# proyecto.net
KiCad netlist of a schematic drawn in EAGLE
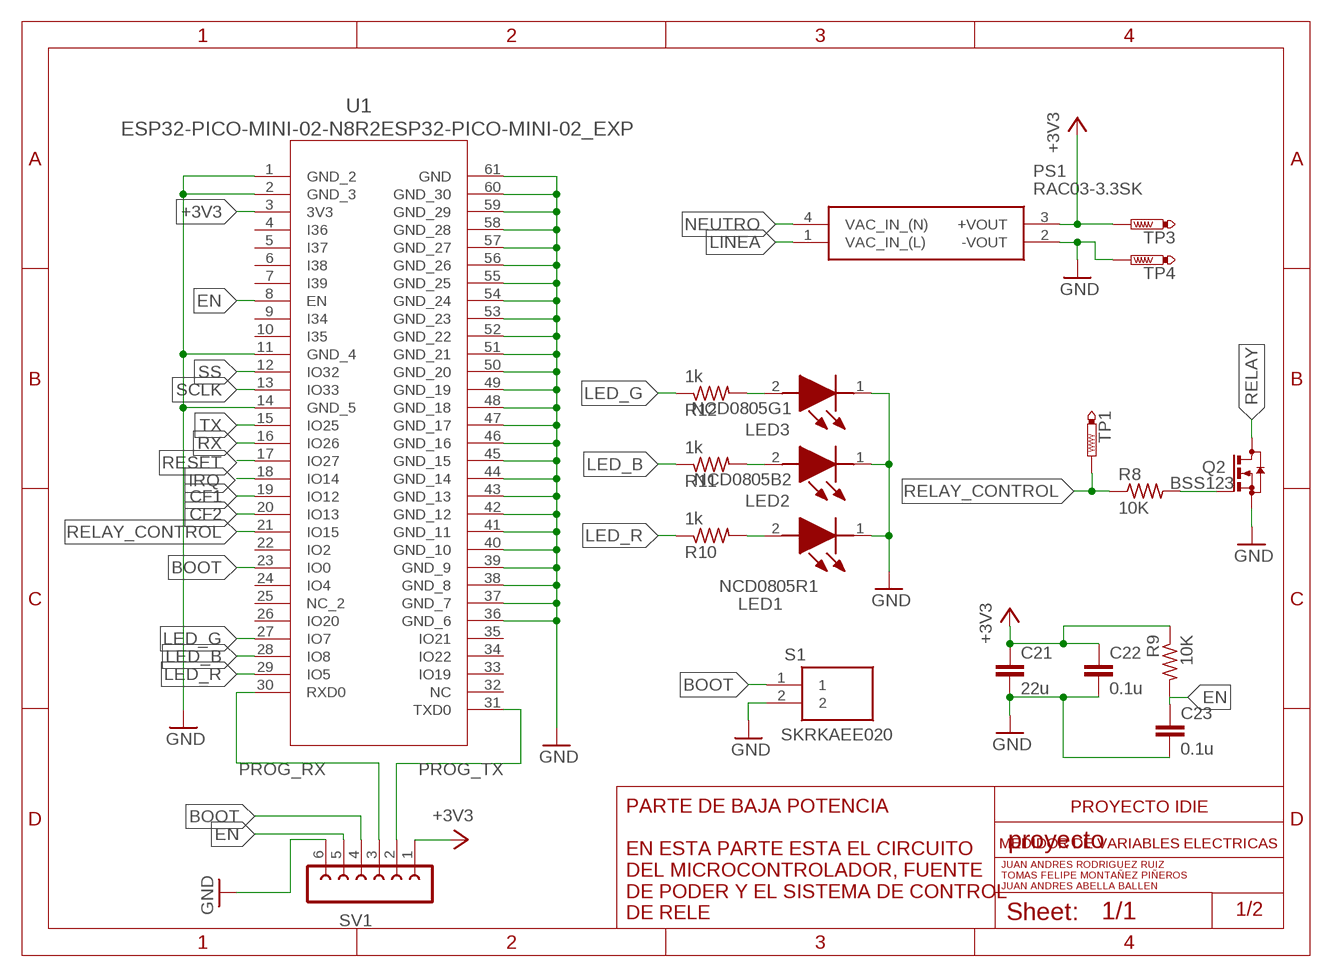
[diagram p0: schematic, sheet 1, part 1 of 2]
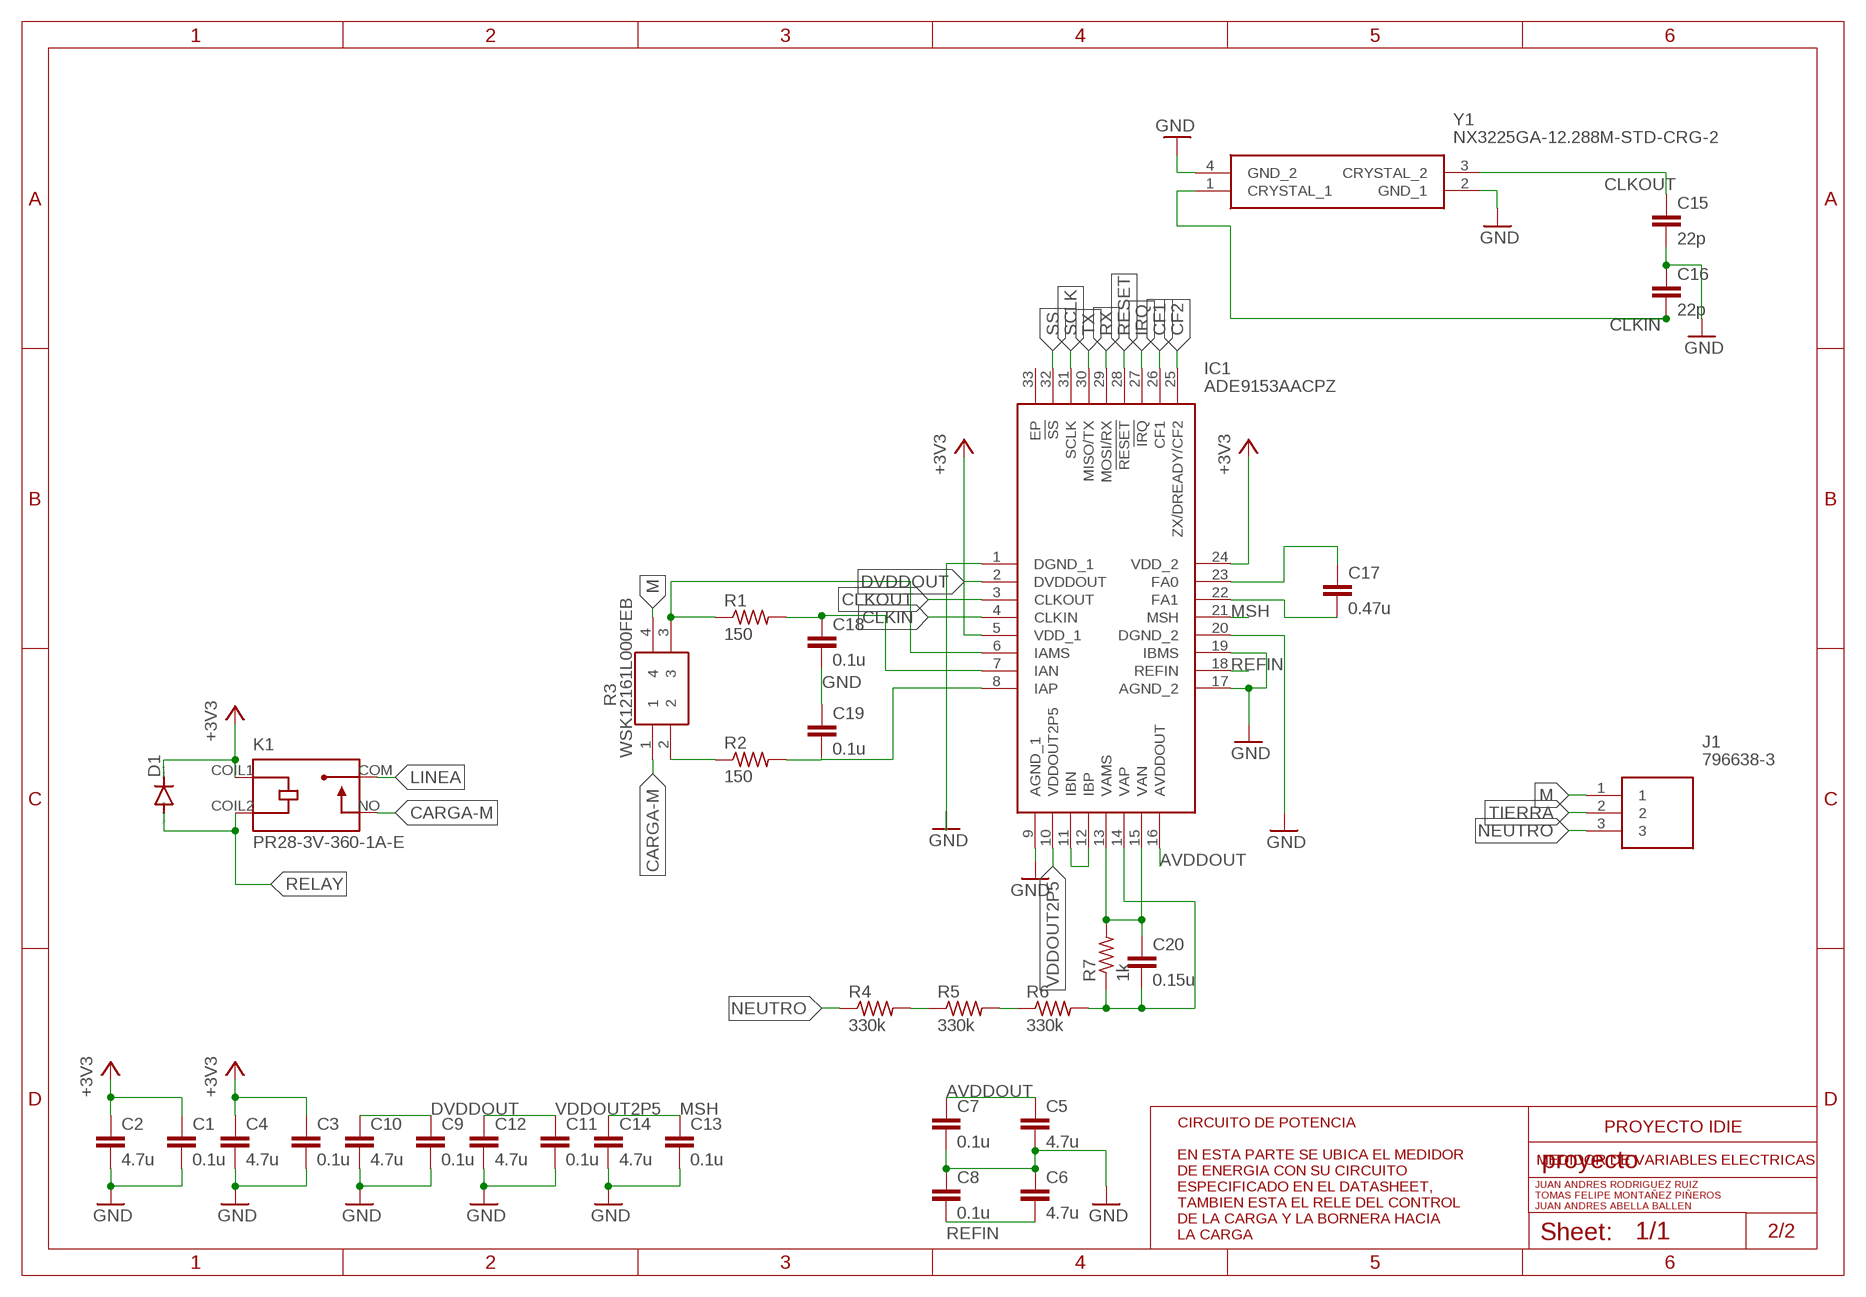
[diagram p1: schematic, sheet 1, part 2 of 2]

(export (version "E")
  (design (tool "Eeschema 10.0.6"))
  (components
    (comp (ref "C1")
      (value "0.1u")
      (footprint "eagle-import:C0402K")
      (libsource (lib "eagle-import") (part "C-EUC0402K"))
    )
    (comp (ref "C2")
      (value "4.7u")
      (footprint "eagle-import:C0402K")
      (libsource (lib "eagle-import") (part "C-EUC0402K"))
    )
    (comp (ref "C3")
      (value "0.1u")
      (footprint "eagle-import:C0402K")
      (libsource (lib "eagle-import") (part "C-EUC0402K"))
    )
    (comp (ref "C4")
      (value "4.7u")
      (footprint "eagle-import:C0402K")
      (libsource (lib "eagle-import") (part "C-EUC0402K"))
    )
    (comp (ref "C5")
      (value "4.7u")
      (footprint "eagle-import:C0402K")
      (libsource (lib "eagle-import") (part "C-EUC0402K"))
    )
    (comp (ref "C6")
      (value "4.7u")
      (footprint "eagle-import:C0402K")
      (libsource (lib "eagle-import") (part "C-EUC0402K"))
    )
    (comp (ref "C7")
      (value "0.1u")
      (footprint "eagle-import:C0402K")
      (libsource (lib "eagle-import") (part "C-EUC0402K"))
    )
    (comp (ref "C8")
      (value "0.1u")
      (footprint "eagle-import:C0402K")
      (libsource (lib "eagle-import") (part "C-EUC0402K"))
    )
    (comp (ref "C9")
      (value "0.1u")
      (footprint "eagle-import:C0402K")
      (libsource (lib "eagle-import") (part "C-EUC0402K"))
    )
    (comp (ref "C10")
      (value "4.7u")
      (footprint "eagle-import:C0402K")
      (libsource (lib "eagle-import") (part "C-EUC0402K"))
    )
    (comp (ref "C11")
      (value "0.1u")
      (footprint "eagle-import:C0402K")
      (libsource (lib "eagle-import") (part "C-EUC0402K"))
    )
    (comp (ref "C12")
      (value "4.7u")
      (footprint "eagle-import:C0402K")
      (libsource (lib "eagle-import") (part "C-EUC0402K"))
    )
    (comp (ref "C13")
      (value "0.1u")
      (footprint "eagle-import:C0402K")
      (libsource (lib "eagle-import") (part "C-EUC0402K"))
    )
    (comp (ref "C14")
      (value "4.7u")
      (footprint "eagle-import:C0402K")
      (libsource (lib "eagle-import") (part "C-EUC0402K"))
    )
    (comp (ref "C15")
      (value "22p")
      (footprint "eagle-import:C0402K")
      (libsource (lib "eagle-import") (part "C-EUC0402K"))
    )
    (comp (ref "C16")
      (value "22p")
      (footprint "eagle-import:C0402K")
      (libsource (lib "eagle-import") (part "C-EUC0402K"))
    )
    (comp (ref "C17")
      (value "0.47u")
      (footprint "eagle-import:C0402K")
      (libsource (lib "eagle-import") (part "C-EUC0402K"))
    )
    (comp (ref "C18")
      (value "0.1u")
      (footprint "eagle-import:C0402K")
      (libsource (lib "eagle-import") (part "C-EUC0402K"))
    )
    (comp (ref "C19")
      (value "0.1u")
      (footprint "eagle-import:C0402K")
      (libsource (lib "eagle-import") (part "C-EUC0402K"))
    )
    (comp (ref "C20")
      (value "0.15u")
      (footprint "eagle-import:C0402K")
      (libsource (lib "eagle-import") (part "C-EUC0402K"))
    )
    (comp (ref "C21")
      (value "22u")
      (footprint "eagle-import:C0402K")
      (libsource (lib "eagle-import") (part "C-EUC0402K"))
    )
    (comp (ref "C22")
      (value "0.1u")
      (footprint "eagle-import:C0402K")
      (libsource (lib "eagle-import") (part "C-EUC0402K"))
    )
    (comp (ref "C23")
      (value "0.1u")
      (footprint "eagle-import:C0402K")
      (libsource (lib "eagle-import") (part "C-EUC0402K"))
    )
    (comp (ref "D1")
      (value "DIODE-SMB")
      (footprint "eagle-import:SMB")
      (libsource (lib "eagle-import") (part "DIODE-SMB"))
    )
    (comp (ref "IC1")
      (value "ADE9153AACPZ")
      (footprint "eagle-import:QFN50P500X500X80-33N")
      (fields (field (name "MOUSER_PART_NUMBER") "584-ADE9153AACPZ"))
      (libsource (lib "eagle-import") (part "ADE9153AACPZ"))
    )
    (comp (ref "J1")
      (value "796638-3")
      (footprint "eagle-import:SHDRRA3W102P0X508_1X3_1706X120")
      (fields (field (name "MOUSER_PART_NUMBER") "571-7966383"))
      (libsource (lib "eagle-import") (part "796638-3"))
    )
    (comp (ref "K1")
      (value "PR28-3V-360-1A-E")
      (footprint "eagle-import:RELAY_PR28-3V-360-1A-E")
      (fields (field (name "MF") "CUI Devices"))
      (libsource (lib "eagle-import") (part "PR28-3V-360-1A-E"))
    )
    (comp (ref "LED1")
      (value "NCD0805R1")
      (footprint "eagle-import:LEDC2012X120N")
      (libsource (lib "eagle-import") (part "NCD0805R1"))
    )
    (comp (ref "LED2")
      (value "NCD0805B2")
      (footprint "eagle-import:LEDC2012X120N")
      (libsource (lib "eagle-import") (part "NCD0805B2"))
    )
    (comp (ref "LED3")
      (value "NCD0805G1")
      (footprint "eagle-import:LEDC2012X120N")
      (libsource (lib "eagle-import") (part "NCD0805G1"))
    )
    (comp (ref "PS1")
      (value "RAC03-3.3SK")
      (footprint "eagle-import:RAC0305SK")
      (fields (field (name "MOUSER_PART_NUMBER") "919-RAC03-3.3SK"))
      (libsource (lib "eagle-import") (part "RAC03-3.3SK"))
    )
    (comp (ref "Q2")
      (value "BSS123")
      (footprint "eagle-import:SOT23")
      (libsource (lib "eagle-import") (part "BSS123"))
    )
    (comp (ref "R1")
      (value "150")
      (footprint "eagle-import:R0402")
      (libsource (lib "eagle-import") (part "R-US_R0402"))
    )
    (comp (ref "R2")
      (value "150")
      (footprint "eagle-import:R0402")
      (libsource (lib "eagle-import") (part "R-US_R0402"))
    )
    (comp (ref "R3")
      (value "WSK12161L000FEB")
      (footprint "eagle-import:WSK12161L000FEB")
      (fields (field (name "MOUSER_PART_NUMBER") "71-WSK12161L000FEB"))
      (libsource (lib "eagle-import") (part "WSK12161L000FEB"))
    )
    (comp (ref "R4")
      (value "330k")
      (footprint "eagle-import:R0603")
      (libsource (lib "eagle-import") (part "R-US_R0603"))
    )
    (comp (ref "R5")
      (value "330k")
      (footprint "eagle-import:R0603")
      (libsource (lib "eagle-import") (part "R-US_R0603"))
    )
    (comp (ref "R6")
      (value "330k")
      (footprint "eagle-import:R0603")
      (libsource (lib "eagle-import") (part "R-US_R0603"))
    )
    (comp (ref "R7")
      (value "1k")
      (footprint "eagle-import:R0603")
      (libsource (lib "eagle-import") (part "R-US_R0603"))
    )
    (comp (ref "R8")
      (value "10K")
      (footprint "eagle-import:R0402")
      (libsource (lib "eagle-import") (part "R-US_R0402"))
    )
    (comp (ref "R9")
      (value "10K")
      (footprint "eagle-import:R0402")
      (libsource (lib "eagle-import") (part "R-US_R0402"))
    )
    (comp (ref "R10")
      (value "1k")
      (footprint "eagle-import:R0402")
      (libsource (lib "eagle-import") (part "R-US_R0402"))
    )
    (comp (ref "R11")
      (value "1k")
      (footprint "eagle-import:R0402")
      (libsource (lib "eagle-import") (part "R-US_R0402"))
    )
    (comp (ref "R12")
      (value "1k")
      (footprint "eagle-import:R0402")
      (libsource (lib "eagle-import") (part "R-US_R0402"))
    )
    (comp (ref "S1")
      (value "SKRKAEE020")
      (footprint "eagle-import:SKRKAEE020")
      (fields (field (name "MOUSER_PART_NUMBER") "688-SKRKAEE020"))
      (libsource (lib "eagle-import") (part "SKRKAEE020"))
    )
    (comp (ref "SV1")
      (value "FE06-1")
      (footprint "eagle-import:FE06")
      (libsource (lib "eagle-import") (part "FE06-1"))
    )
    (comp (ref "TP1")
      (value "PTR1TP10R")
      (footprint "eagle-import:TP10R")
      (libsource (lib "eagle-import") (part "PTR1TP10R"))
    )
    (comp (ref "TP3")
      (value "PTR1TP10R")
      (footprint "eagle-import:TP10R")
      (libsource (lib "eagle-import") (part "PTR1TP10R"))
    )
    (comp (ref "TP4")
      (value "PTR1TP10R")
      (footprint "eagle-import:TP10R")
      (libsource (lib "eagle-import") (part "PTR1TP10R"))
    )
    (comp (ref "U1")
      (value "ESP32-PICO-MINI-02-N8R2ESP32-PICO-MINI-02_EXP")
      (footprint "eagle-import:ESP32-PICO-MINI-02_EXP")
      (fields
        (field (name "MANUFACTURER_PART_NUMBER") "ESP32-PICO-MINI-02-N8R2")
        (field (name "COPYRIGHT") "Copyright (C) 2024 Ultra Librarian. All rights reserved.")
      )
      (libsource (lib "eagle-import") (part "ESP32-PICO-MINI-02-N8R2ESP32-PICO-MINI-02_EXP"))
    )
    (comp (ref "Y1")
      (value "NX3225GA-12.288M-STD-CRG-2")
      (footprint "eagle-import:NX3225GA12288MSTDCRG2")
      (libsource (lib "eagle-import") (part "NX3225GA-12.288M-STD-CRG-2"))
    )
  )
  (nets
    (net (code "1") (name "+3V3") (class "Default")
      (node (ref "C1") (pin "1") (pinfunction "1_1") (pintype "passive"))
      (node (ref "C2") (pin "1") (pinfunction "1_1") (pintype "passive"))
      (node (ref "C21") (pin "1") (pinfunction "1_1") (pintype "passive"))
      (node (ref "C22") (pin "1") (pinfunction "1_1") (pintype "passive"))
      (node (ref "C3") (pin "1") (pinfunction "1_1") (pintype "passive"))
      (node (ref "C4") (pin "1") (pinfunction "1_1") (pintype "passive"))
      (node (ref "D1") (pin "C") (pinfunction "C_C") (pintype "passive"))
      (node (ref "IC1") (pin "24") (pinfunction "VDD_2_24") (pintype "bidirectional"))
      (node (ref "IC1") (pin "5") (pinfunction "VDD_1_5") (pintype "bidirectional"))
      (node (ref "K1") (pin "COIL1") (pinfunction "COIL1_COIL1") (pintype "passive"))
      (node (ref "PS1") (pin "3") (pinfunction "+VOUT_3") (pintype "bidirectional"))
      (node (ref "R9") (pin "1") (pinfunction "1_1") (pintype "passive"))
      (node (ref "SV1") (pin "1") (pinfunction "1_1") (pintype "passive"))
      (node (ref "TP3") (pin "TP") (pinfunction "TP_TP") (pintype "input"))
      (node (ref "U1") (pin "3") (pinfunction "3V3_3") (pintype "power_in"))
    )
    (net (code "2") (name "/AVDDOUT") (class "Default")
      (node (ref "C5") (pin "1") (pinfunction "1_1") (pintype "passive"))
      (node (ref "C7") (pin "1") (pinfunction "1_1") (pintype "passive"))
      (node (ref "IC1") (pin "16") (pinfunction "AVDDOUT_16") (pintype "bidirectional"))
    )
    (net (code "3") (name "/MSH") (class "Default")
      (node (ref "C13") (pin "1") (pinfunction "1_1") (pintype "passive"))
      (node (ref "C14") (pin "1") (pinfunction "1_1") (pintype "passive"))
      (node (ref "IC1") (pin "21") (pinfunction "MSH_21") (pintype "bidirectional"))
    )
    (net (code "4") (name "/PROG_RX") (class "Default")
      (node (ref "SV1") (pin "3") (pinfunction "3_3") (pintype "passive"))
      (node (ref "U1") (pin "30") (pinfunction "RXD0_30") (pintype "bidirectional"))
    )
    (net (code "5") (name "/PROG_TX") (class "Default")
      (node (ref "SV1") (pin "2") (pinfunction "2_2") (pintype "passive"))
      (node (ref "U1") (pin "31") (pinfunction "TXD0_31") (pintype "bidirectional"))
    )
    (net (code "6") (name "/REFIN") (class "Default")
      (node (ref "C6") (pin "2") (pinfunction "2_2") (pintype "passive"))
      (node (ref "C8") (pin "2") (pinfunction "2_2") (pintype "passive"))
      (node (ref "IC1") (pin "18") (pinfunction "REFIN_18") (pintype "bidirectional"))
    )
    (net (code "7") (name "BOOT") (class "Default")
      (node (ref "S1") (pin "1") (pinfunction "1_1") (pintype "bidirectional"))
      (node (ref "SV1") (pin "4") (pinfunction "4_4") (pintype "passive"))
      (node (ref "U1") (pin "23") (pinfunction "IO0_23") (pintype "bidirectional"))
    )
    (net (code "8") (name "CARGA-M") (class "Default")
      (node (ref "K1") (pin "NO") (pinfunction "NO_NO") (pintype "passive"))
      (node (ref "R3") (pin "1") (pinfunction "1_1") (pintype "bidirectional"))
    )
    (net (code "9") (name "CF1") (class "Default")
      (node (ref "IC1") (pin "26") (pinfunction "CF1_26") (pintype "bidirectional"))
      (node (ref "U1") (pin "19") (pinfunction "IO12_19") (pintype "bidirectional"))
    )
    (net (code "10") (name "CF2") (class "Default")
      (node (ref "IC1") (pin "25") (pinfunction "ZX/DREADY/CF2_25") (pintype "bidirectional"))
      (node (ref "U1") (pin "20") (pinfunction "IO13_20") (pintype "bidirectional"))
    )
    (net (code "11") (name "CLKIN") (class "Default")
      (node (ref "C16") (pin "2") (pinfunction "2_2") (pintype "passive"))
      (node (ref "IC1") (pin "4") (pinfunction "CLKIN_4") (pintype "bidirectional"))
      (node (ref "Y1") (pin "1") (pinfunction "CRYSTAL_1_1") (pintype "bidirectional"))
    )
    (net (code "12") (name "CLKOUT") (class "Default")
      (node (ref "C15") (pin "1") (pinfunction "1_1") (pintype "passive"))
      (node (ref "IC1") (pin "3") (pinfunction "CLKOUT_3") (pintype "bidirectional"))
      (node (ref "Y1") (pin "3") (pinfunction "CRYSTAL_2_3") (pintype "bidirectional"))
    )
    (net (code "13") (name "DVDDOUT") (class "Default")
      (node (ref "C10") (pin "1") (pinfunction "1_1") (pintype "passive"))
      (node (ref "C9") (pin "1") (pinfunction "1_1") (pintype "passive"))
      (node (ref "IC1") (pin "2") (pinfunction "DVDDOUT_2") (pintype "bidirectional"))
    )
    (net (code "14") (name "EN") (class "Default")
      (node (ref "C23") (pin "1") (pinfunction "1_1") (pintype "passive"))
      (node (ref "R9") (pin "2") (pinfunction "2_2") (pintype "passive"))
      (node (ref "SV1") (pin "5") (pinfunction "5_5") (pintype "passive"))
      (node (ref "U1") (pin "8") (pinfunction "EN_8") (pintype "input"))
    )
    (net (code "15") (name "GND") (class "Default")
      (node (ref "C1") (pin "2") (pinfunction "2_2") (pintype "passive"))
      (node (ref "C10") (pin "2") (pinfunction "2_2") (pintype "passive"))
      (node (ref "C11") (pin "2") (pinfunction "2_2") (pintype "passive"))
      (node (ref "C12") (pin "2") (pinfunction "2_2") (pintype "passive"))
      (node (ref "C13") (pin "2") (pinfunction "2_2") (pintype "passive"))
      (node (ref "C14") (pin "2") (pinfunction "2_2") (pintype "passive"))
      (node (ref "C15") (pin "2") (pinfunction "2_2") (pintype "passive"))
      (node (ref "C16") (pin "1") (pinfunction "1_1") (pintype "passive"))
      (node (ref "C18") (pin "2") (pinfunction "2_2") (pintype "passive"))
      (node (ref "C19") (pin "1") (pinfunction "1_1") (pintype "passive"))
      (node (ref "C2") (pin "2") (pinfunction "2_2") (pintype "passive"))
      (node (ref "C21") (pin "2") (pinfunction "2_2") (pintype "passive"))
      (node (ref "C22") (pin "2") (pinfunction "2_2") (pintype "passive"))
      (node (ref "C23") (pin "2") (pinfunction "2_2") (pintype "passive"))
      (node (ref "C3") (pin "2") (pinfunction "2_2") (pintype "passive"))
      (node (ref "C4") (pin "2") (pinfunction "2_2") (pintype "passive"))
      (node (ref "C5") (pin "2") (pinfunction "2_2") (pintype "passive"))
      (node (ref "C6") (pin "1") (pinfunction "1_1") (pintype "passive"))
      (node (ref "C7") (pin "2") (pinfunction "2_2") (pintype "passive"))
      (node (ref "C8") (pin "1") (pinfunction "1_1") (pintype "passive"))
      (node (ref "C9") (pin "2") (pinfunction "2_2") (pintype "passive"))
      (node (ref "IC1") (pin "1") (pinfunction "DGND_1_1") (pintype "bidirectional"))
      (node (ref "IC1") (pin "17") (pinfunction "AGND_2_17") (pintype "bidirectional"))
      (node (ref "IC1") (pin "19") (pinfunction "IBMS_19") (pintype "bidirectional"))
      (node (ref "IC1") (pin "20") (pinfunction "DGND_2_20") (pintype "bidirectional"))
      (node (ref "IC1") (pin "9") (pinfunction "AGND_1_9") (pintype "bidirectional"))
      (node (ref "LED1") (pin "1") (pinfunction "K_1") (pintype "bidirectional"))
      (node (ref "LED2") (pin "1") (pinfunction "K_1") (pintype "bidirectional"))
      (node (ref "LED3") (pin "1") (pinfunction "K_1") (pintype "bidirectional"))
      (node (ref "PS1") (pin "2") (pinfunction "-VOUT_2") (pintype "bidirectional"))
      (node (ref "Q2") (pin "2") (pinfunction "S_2") (pintype "passive"))
      (node (ref "S1") (pin "2") (pinfunction "2_2") (pintype "bidirectional"))
      (node (ref "SV1") (pin "6") (pinfunction "6_6") (pintype "passive"))
      (node (ref "TP4") (pin "TP") (pinfunction "TP_TP") (pintype "input"))
      (node (ref "U1") (pin "1") (pinfunction "GND_2_1") (pintype "passive"))
      (node (ref "U1") (pin "11") (pinfunction "GND_4_11") (pintype "passive"))
      (node (ref "U1") (pin "14") (pinfunction "GND_5_14") (pintype "passive"))
      (node (ref "U1") (pin "2") (pinfunction "GND_3_2") (pintype "passive"))
      (node (ref "U1") (pin "36") (pinfunction "GND_6_36") (pintype "passive"))
      (node (ref "U1") (pin "37") (pinfunction "GND_7_37") (pintype "passive"))
      (node (ref "U1") (pin "38") (pinfunction "GND_8_38") (pintype "passive"))
      (node (ref "U1") (pin "39") (pinfunction "GND_9_39") (pintype "passive"))
      (node (ref "U1") (pin "40") (pinfunction "GND_10_40") (pintype "passive"))
      (node (ref "U1") (pin "41") (pinfunction "GND_11_41") (pintype "passive"))
      (node (ref "U1") (pin "42") (pinfunction "GND_12_42") (pintype "passive"))
      (node (ref "U1") (pin "43") (pinfunction "GND_13_43") (pintype "passive"))
      (node (ref "U1") (pin "44") (pinfunction "GND_14_44") (pintype "passive"))
      (node (ref "U1") (pin "45") (pinfunction "GND_15_45") (pintype "passive"))
      (node (ref "U1") (pin "46") (pinfunction "GND_16_46") (pintype "passive"))
      (node (ref "U1") (pin "47") (pinfunction "GND_17_47") (pintype "passive"))
      (node (ref "U1") (pin "48") (pinfunction "GND_18_48") (pintype "passive"))
      (node (ref "U1") (pin "49") (pinfunction "GND_19_49") (pintype "passive"))
      (node (ref "U1") (pin "50") (pinfunction "GND_20_50") (pintype "passive"))
      (node (ref "U1") (pin "51") (pinfunction "GND_21_51") (pintype "passive"))
      (node (ref "U1") (pin "52") (pinfunction "GND_22_52") (pintype "passive"))
      (node (ref "U1") (pin "53") (pinfunction "GND_23_53") (pintype "passive"))
      (node (ref "U1") (pin "54") (pinfunction "GND_24_54") (pintype "passive"))
      (node (ref "U1") (pin "55") (pinfunction "GND_25_55") (pintype "passive"))
      (node (ref "U1") (pin "56") (pinfunction "GND_26_56") (pintype "passive"))
      (node (ref "U1") (pin "57") (pinfunction "GND_27_57") (pintype "passive"))
      (node (ref "U1") (pin "58") (pinfunction "GND_28_58") (pintype "passive"))
      (node (ref "U1") (pin "59") (pinfunction "GND_29_59") (pintype "passive"))
      (node (ref "U1") (pin "60") (pinfunction "GND_30_60") (pintype "passive"))
      (node (ref "U1") (pin "61") (pinfunction "GND_61") (pintype "passive"))
      (node (ref "Y1") (pin "2") (pinfunction "GND_1_2") (pintype "bidirectional"))
      (node (ref "Y1") (pin "4") (pinfunction "GND_2_4") (pintype "bidirectional"))
    )
    (net (code "16") (name "IRQ") (class "Default")
      (node (ref "IC1") (pin "27") (pinfunction "~{IRQ}_27") (pintype "bidirectional"))
      (node (ref "U1") (pin "18") (pinfunction "IO14_18") (pintype "bidirectional"))
    )
    (net (code "17") (name "LED_B") (class "Default")
      (node (ref "R11") (pin "1") (pinfunction "1_1") (pintype "passive"))
      (node (ref "U1") (pin "28") (pinfunction "IO8_28") (pintype "bidirectional"))
    )
    (net (code "18") (name "LED_G") (class "Default")
      (node (ref "R12") (pin "1") (pinfunction "1_1") (pintype "passive"))
      (node (ref "U1") (pin "27") (pinfunction "IO7_27") (pintype "bidirectional"))
    )
    (net (code "19") (name "LED_R") (class "Default")
      (node (ref "R10") (pin "1") (pinfunction "1_1") (pintype "passive"))
      (node (ref "U1") (pin "29") (pinfunction "IO5_29") (pintype "bidirectional"))
    )
    (net (code "20") (name "LINEA") (class "Default")
      (node (ref "K1") (pin "COM") (pinfunction "COM_COM") (pintype "passive"))
      (node (ref "PS1") (pin "1") (pinfunction "VAC_IN_(L)_1") (pintype "bidirectional"))
    )
    (net (code "21") (name "M") (class "Default")
      (node (ref "J1") (pin "1") (pinfunction "1_1") (pintype "bidirectional"))
      (node (ref "R3") (pin "4") (pinfunction "4_4") (pintype "bidirectional"))
    )
    (net (code "22") (name "NEUTRO") (class "Default")
      (node (ref "J1") (pin "3") (pinfunction "3_3") (pintype "bidirectional"))
      (node (ref "PS1") (pin "4") (pinfunction "VAC_IN_(N)_4") (pintype "bidirectional"))
      (node (ref "R4") (pin "1") (pinfunction "1_1") (pintype "passive"))
    )
    (net (code "23") (name "Net-(IC1-FA0)") (class "Default")
      (node (ref "C17") (pin "1") (pinfunction "1_1") (pintype "passive"))
      (node (ref "IC1") (pin "23") (pinfunction "FA0_23") (pintype "bidirectional"))
    )
    (net (code "24") (name "Net-(IC1-FA1)") (class "Default")
      (node (ref "C17") (pin "2") (pinfunction "2_2") (pintype "passive"))
      (node (ref "IC1") (pin "22") (pinfunction "FA1_22") (pintype "bidirectional"))
    )
    (net (code "25") (name "Net-(IC1-IAMS)") (class "Default")
      (node (ref "IC1") (pin "6") (pinfunction "IAMS_6") (pintype "bidirectional"))
      (node (ref "R1") (pin "1") (pinfunction "1_1") (pintype "passive"))
      (node (ref "R3") (pin "3") (pinfunction "3_3") (pintype "bidirectional"))
    )
    (net (code "26") (name "Net-(IC1-IAN)") (class "Default")
      (node (ref "C18") (pin "1") (pinfunction "1_1") (pintype "passive"))
      (node (ref "IC1") (pin "7") (pinfunction "IAN_7") (pintype "bidirectional"))
      (node (ref "R1") (pin "2") (pinfunction "2_2") (pintype "passive"))
    )
    (net (code "27") (name "Net-(IC1-IAP)") (class "Default")
      (node (ref "C19") (pin "2") (pinfunction "2_2") (pintype "passive"))
      (node (ref "IC1") (pin "8") (pinfunction "IAP_8") (pintype "bidirectional"))
      (node (ref "R2") (pin "2") (pinfunction "2_2") (pintype "passive"))
    )
    (net (code "28") (name "Net-(IC1-IBN)") (class "Default")
      (node (ref "IC1") (pin "11") (pinfunction "IBN_11") (pintype "bidirectional"))
      (node (ref "IC1") (pin "12") (pinfunction "IBP_12") (pintype "bidirectional"))
    )
    (net (code "29") (name "Net-(IC1-VAMS)") (class "Default")
      (node (ref "C20") (pin "1") (pinfunction "1_1") (pintype "passive"))
      (node (ref "IC1") (pin "13") (pinfunction "VAMS_13") (pintype "bidirectional"))
      (node (ref "IC1") (pin "15") (pinfunction "VAN_15") (pintype "bidirectional"))
      (node (ref "R7") (pin "2") (pinfunction "2_2") (pintype "passive"))
    )
    (net (code "30") (name "Net-(IC1-VAP)") (class "Default")
      (node (ref "C20") (pin "2") (pinfunction "2_2") (pintype "passive"))
      (node (ref "IC1") (pin "14") (pinfunction "VAP_14") (pintype "bidirectional"))
      (node (ref "R6") (pin "2") (pinfunction "2_2") (pintype "passive"))
      (node (ref "R7") (pin "1") (pinfunction "1_1") (pintype "passive"))
    )
    (net (code "31") (name "Net-(LED1-A)") (class "Default")
      (node (ref "LED1") (pin "2") (pinfunction "A_2") (pintype "bidirectional"))
      (node (ref "R10") (pin "2") (pinfunction "2_2") (pintype "passive"))
    )
    (net (code "32") (name "Net-(LED2-A)") (class "Default")
      (node (ref "LED2") (pin "2") (pinfunction "A_2") (pintype "bidirectional"))
      (node (ref "R11") (pin "2") (pinfunction "2_2") (pintype "passive"))
    )
    (net (code "33") (name "Net-(LED3-A)") (class "Default")
      (node (ref "LED3") (pin "2") (pinfunction "A_2") (pintype "bidirectional"))
      (node (ref "R12") (pin "2") (pinfunction "2_2") (pintype "passive"))
    )
    (net (code "34") (name "Net-(Q2-G)") (class "Default")
      (node (ref "Q2") (pin "1") (pinfunction "G_1") (pintype "passive"))
      (node (ref "R8") (pin "2") (pinfunction "2_2") (pintype "passive"))
    )
    (net (code "35") (name "Net-(R2-Pad1)") (class "Default")
      (node (ref "R2") (pin "1") (pinfunction "1_1") (pintype "passive"))
      (node (ref "R3") (pin "2") (pinfunction "2_2") (pintype "bidirectional"))
    )
    (net (code "36") (name "Net-(R4-Pad2)") (class "Default")
      (node (ref "R4") (pin "2") (pinfunction "2_2") (pintype "passive"))
      (node (ref "R5") (pin "1") (pinfunction "1_1") (pintype "passive"))
    )
    (net (code "37") (name "Net-(R5-Pad2)") (class "Default")
      (node (ref "R5") (pin "2") (pinfunction "2_2") (pintype "passive"))
      (node (ref "R6") (pin "1") (pinfunction "1_1") (pintype "passive"))
    )
    (net (code "38") (name "RELAY") (class "Default")
      (node (ref "D1") (pin "A") (pinfunction "A_A") (pintype "passive"))
      (node (ref "K1") (pin "COIL2") (pinfunction "COIL2_COIL2") (pintype "passive"))
      (node (ref "Q2") (pin "3") (pinfunction "D_3") (pintype "passive"))
    )
    (net (code "39") (name "RELAY_CONTROL") (class "Default")
      (node (ref "R8") (pin "1") (pinfunction "1_1") (pintype "passive"))
      (node (ref "TP1") (pin "TP") (pinfunction "TP_TP") (pintype "input"))
      (node (ref "U1") (pin "21") (pinfunction "IO15_21") (pintype "bidirectional"))
    )
    (net (code "40") (name "RESET") (class "Default")
      (node (ref "IC1") (pin "28") (pinfunction "~{RESET}_28") (pintype "bidirectional"))
      (node (ref "U1") (pin "17") (pinfunction "IO27_17") (pintype "bidirectional"))
    )
    (net (code "41") (name "RX") (class "Default")
      (node (ref "IC1") (pin "29") (pinfunction "MOSI/RX_29") (pintype "bidirectional"))
      (node (ref "U1") (pin "16") (pinfunction "IO26_16") (pintype "bidirectional"))
    )
    (net (code "42") (name "SCLK") (class "Default")
      (node (ref "IC1") (pin "31") (pinfunction "SCLK_31") (pintype "bidirectional"))
      (node (ref "U1") (pin "13") (pinfunction "IO33_13") (pintype "bidirectional"))
    )
    (net (code "43") (name "SS") (class "Default")
      (node (ref "IC1") (pin "32") (pinfunction "~{SS}_32") (pintype "bidirectional"))
      (node (ref "U1") (pin "12") (pinfunction "IO32_12") (pintype "bidirectional"))
    )
    (net (code "44") (name "TIERRA") (class "Default")
      (node (ref "J1") (pin "2") (pinfunction "2_2") (pintype "bidirectional"))
    )
    (net (code "45") (name "TX") (class "Default")
      (node (ref "IC1") (pin "30") (pinfunction "MISO/TX_30") (pintype "bidirectional"))
      (node (ref "U1") (pin "15") (pinfunction "IO25_15") (pintype "bidirectional"))
    )
    (net (code "46") (name "VDDOUT2P5") (class "Default")
      (node (ref "C11") (pin "1") (pinfunction "1_1") (pintype "passive"))
      (node (ref "C12") (pin "1") (pinfunction "1_1") (pintype "passive"))
      (node (ref "IC1") (pin "10") (pinfunction "VDDOUT2P5_10") (pintype "bidirectional"))
    )
    (net (code "47") (name "unconnected-(IC1-EP-Pad33)") (class "Default")
      (node (ref "IC1") (pin "33") (pinfunction "EP_33") (pintype "bidirectional"))
    )
    (net (code "48") (name "unconnected-(U1-I34-Pad9)") (class "Default")
      (node (ref "U1") (pin "9") (pinfunction "I34_9") (pintype "input"))
    )
    (net (code "49") (name "unconnected-(U1-I35-Pad10)") (class "Default")
      (node (ref "U1") (pin "10") (pinfunction "I35_10") (pintype "input"))
    )
    (net (code "50") (name "unconnected-(U1-I36-Pad4)") (class "Default")
      (node (ref "U1") (pin "4") (pinfunction "I36_4") (pintype "input"))
    )
    (net (code "51") (name "unconnected-(U1-I37-Pad5)") (class "Default")
      (node (ref "U1") (pin "5") (pinfunction "I37_5") (pintype "input"))
    )
    (net (code "52") (name "unconnected-(U1-I38-Pad6)") (class "Default")
      (node (ref "U1") (pin "6") (pinfunction "I38_6") (pintype "input"))
    )
    (net (code "53") (name "unconnected-(U1-I39-Pad7)") (class "Default")
      (node (ref "U1") (pin "7") (pinfunction "I39_7") (pintype "input"))
    )
    (net (code "54") (name "unconnected-(U1-IO2-Pad22)") (class "Default")
      (node (ref "U1") (pin "22") (pinfunction "IO2_22") (pintype "bidirectional"))
    )
    (net (code "55") (name "unconnected-(U1-IO4-Pad24)") (class "Default")
      (node (ref "U1") (pin "24") (pinfunction "IO4_24") (pintype "bidirectional"))
    )
    (net (code "56") (name "unconnected-(U1-IO19-Pad33)") (class "Default")
      (node (ref "U1") (pin "33") (pinfunction "IO19_33") (pintype "bidirectional"))
    )
    (net (code "57") (name "unconnected-(U1-IO20-Pad26)") (class "Default")
      (node (ref "U1") (pin "26") (pinfunction "IO20_26") (pintype "bidirectional"))
    )
    (net (code "58") (name "unconnected-(U1-IO21-Pad35)") (class "Default")
      (node (ref "U1") (pin "35") (pinfunction "IO21_35") (pintype "bidirectional"))
    )
    (net (code "59") (name "unconnected-(U1-IO22-Pad34)") (class "Default")
      (node (ref "U1") (pin "34") (pinfunction "IO22_34") (pintype "bidirectional"))
    )
    (net (code "60") (name "unconnected-(U1-NC-Pad32)") (class "Default")
      (node (ref "U1") (pin "32") (pinfunction "NC_32") (pintype "no_connect"))
    )
    (net (code "61") (name "unconnected-(U1-NC_2-Pad25)") (class "Default")
      (node (ref "U1") (pin "25") (pinfunction "NC_2_25") (pintype "no_connect"))
    )
  )
)
